# 13thISE_ver2.net
KiCad netlist of a schematic drawn in EAGLE
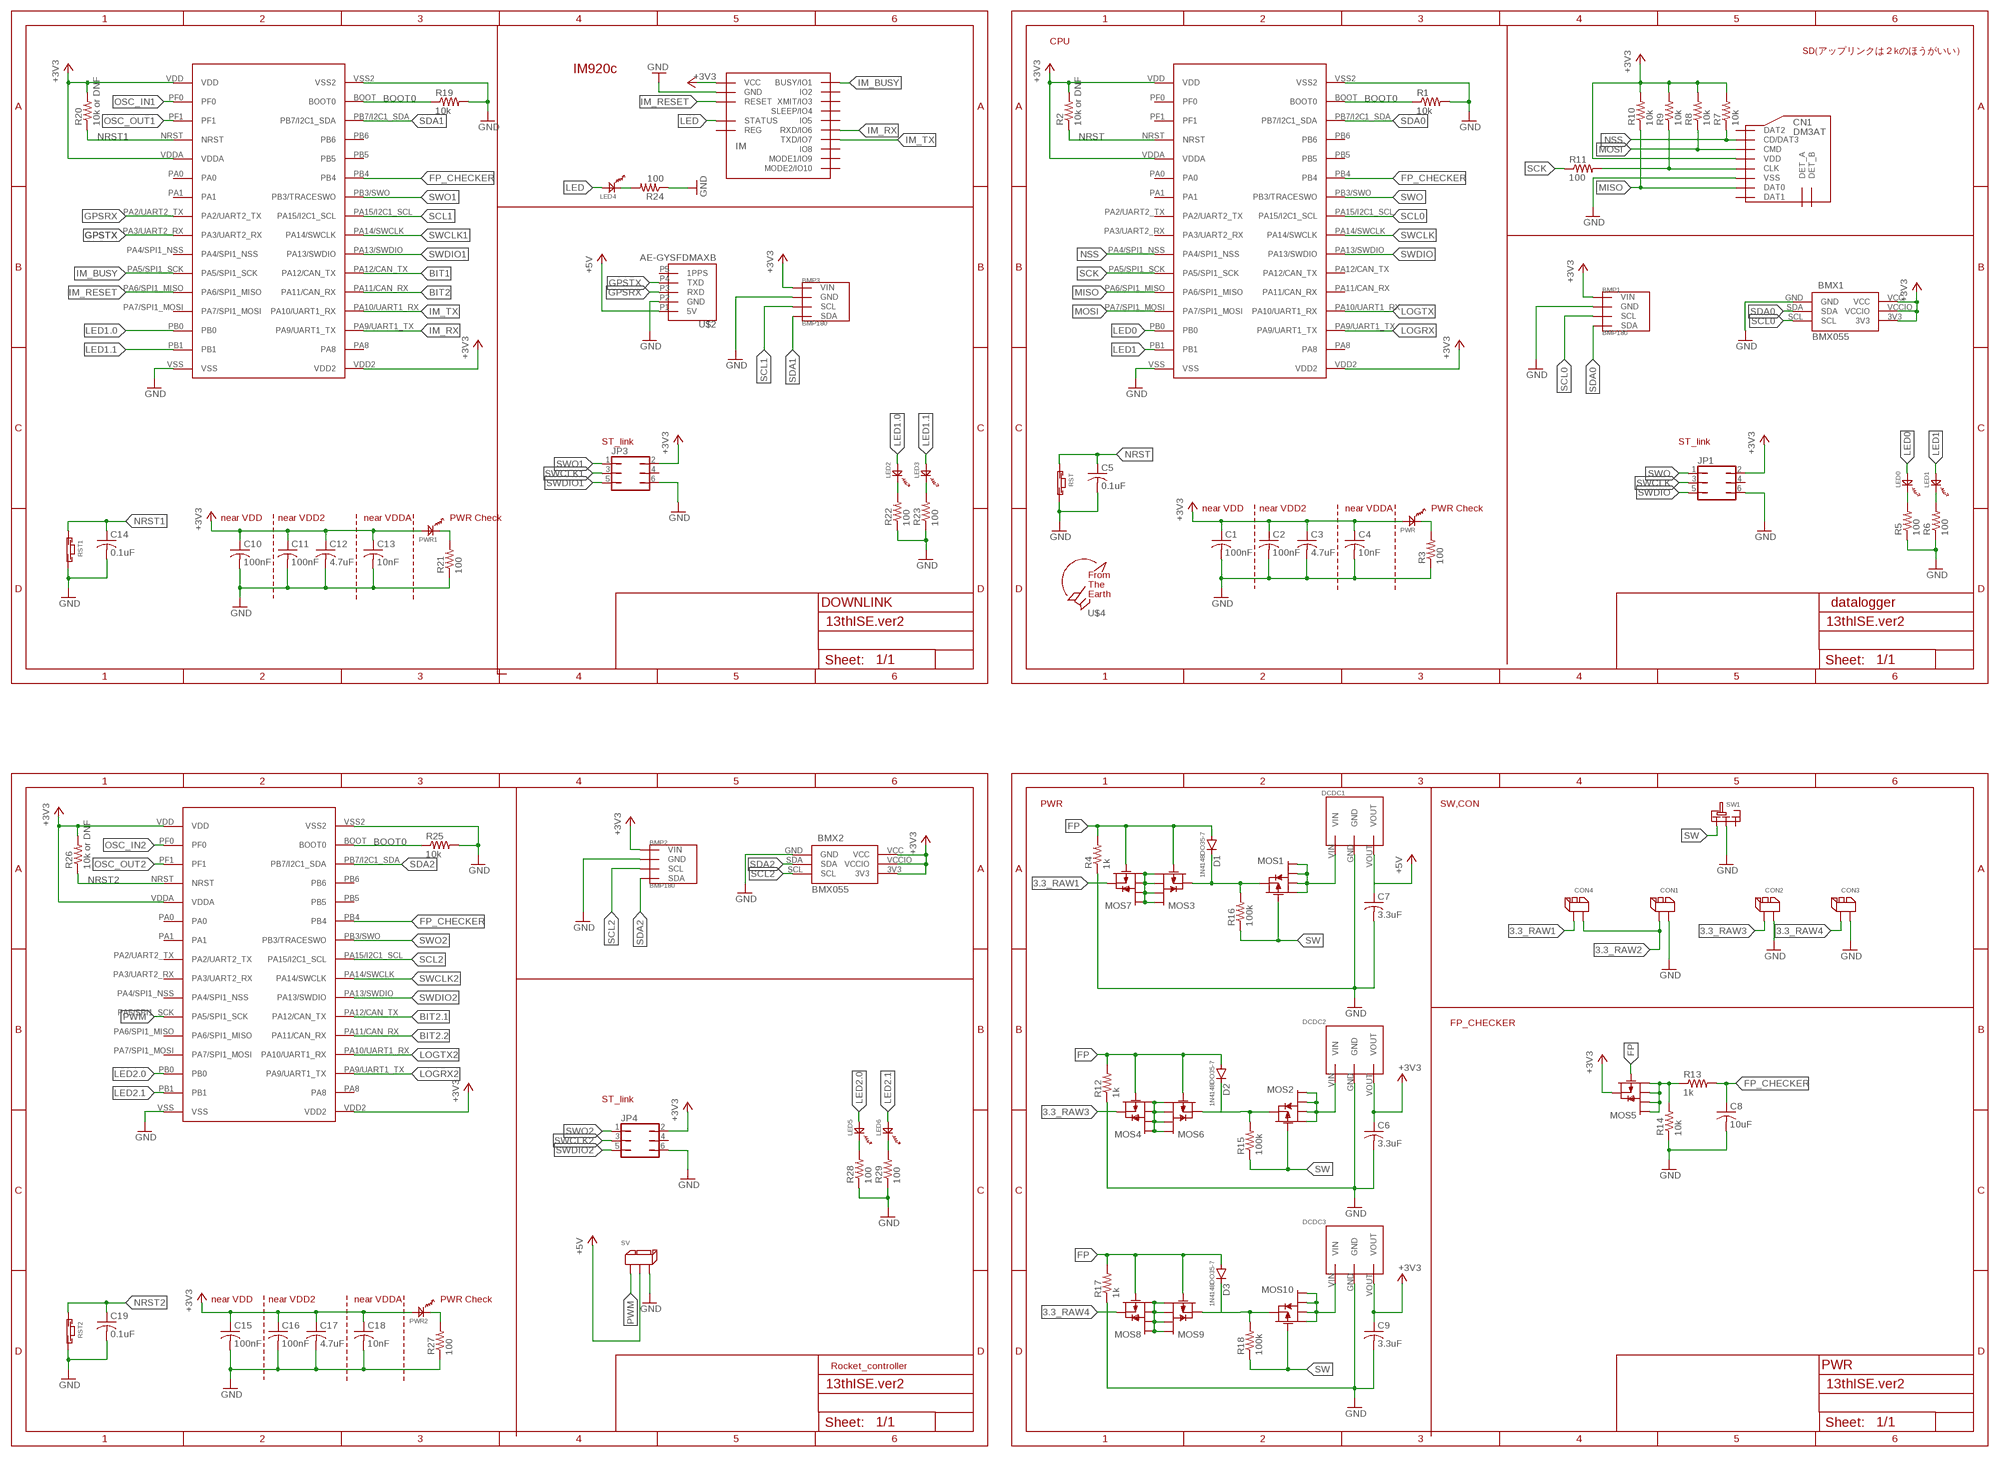
[diagram p0: schematic, sheet 1]

(export (version "E")
  (design (tool "Eeschema 10.0.6"))
  (components
    (comp (ref "BMP1")
      (value "BMP180")
      (footprint "eagle-import:GY-68")
      (libsource (lib "eagle-import") (part "BMP180"))
    )
    (comp (ref "BMP2")
      (value "BMP180")
      (footprint "eagle-import:GY-68")
      (libsource (lib "eagle-import") (part "BMP180"))
    )
    (comp (ref "BMP3")
      (value "BMP180")
      (footprint "eagle-import:GY-68")
      (libsource (lib "eagle-import") (part "BMP180"))
    )
    (comp (ref "BMX1")
      (value "BMX055")
      (footprint "eagle-import:BMX055")
      (libsource (lib "eagle-import") (part "BMX055"))
    )
    (comp (ref "BMX2")
      (value "BMX055")
      (footprint "eagle-import:BMX055")
      (libsource (lib "eagle-import") (part "BMX055"))
    )
    (comp (ref "C1")
      (value "100nF")
      (footprint "eagle-import:C1608")
      (libsource (lib "eagle-import") (part "C-USC1608"))
    )
    (comp (ref "C2")
      (value "100nF")
      (footprint "eagle-import:C1608")
      (libsource (lib "eagle-import") (part "C-USC1608"))
    )
    (comp (ref "C3")
      (value "4.7uF")
      (footprint "eagle-import:C1608")
      (libsource (lib "eagle-import") (part "C-USC1608"))
    )
    (comp (ref "C4")
      (value "10nF")
      (footprint "eagle-import:C1608")
      (libsource (lib "eagle-import") (part "C-USC1608"))
    )
    (comp (ref "C5")
      (value "0.1uF")
      (footprint "eagle-import:C1608")
      (libsource (lib "eagle-import") (part "C-USC1608"))
    )
    (comp (ref "C6")
      (value "3.3uF")
      (footprint "eagle-import:C0603")
      (libsource (lib "eagle-import") (part "C-USC0603"))
    )
    (comp (ref "C7")
      (value "3.3uF")
      (footprint "eagle-import:C0603")
      (libsource (lib "eagle-import") (part "C-USC0603"))
    )
    (comp (ref "C8")
      (value "10uF")
      (footprint "eagle-import:C0603")
      (libsource (lib "eagle-import") (part "C-USC0603"))
    )
    (comp (ref "C9")
      (value "3.3uF")
      (footprint "eagle-import:C0603")
      (libsource (lib "eagle-import") (part "C-USC0603"))
    )
    (comp (ref "C10")
      (value "100nF")
      (footprint "eagle-import:C1608")
      (libsource (lib "eagle-import") (part "C-USC1608"))
    )
    (comp (ref "C11")
      (value "100nF")
      (footprint "eagle-import:C1608")
      (libsource (lib "eagle-import") (part "C-USC1608"))
    )
    (comp (ref "C12")
      (value "4.7uF")
      (footprint "eagle-import:C1608")
      (libsource (lib "eagle-import") (part "C-USC1608"))
    )
    (comp (ref "C13")
      (value "10nF")
      (footprint "eagle-import:C1608")
      (libsource (lib "eagle-import") (part "C-USC1608"))
    )
    (comp (ref "C14")
      (value "0.1uF")
      (footprint "eagle-import:C1608")
      (libsource (lib "eagle-import") (part "C-USC1608"))
    )
    (comp (ref "C15")
      (value "100nF")
      (footprint "eagle-import:C1608")
      (libsource (lib "eagle-import") (part "C-USC1608"))
    )
    (comp (ref "C16")
      (value "100nF")
      (footprint "eagle-import:C1608")
      (libsource (lib "eagle-import") (part "C-USC1608"))
    )
    (comp (ref "C17")
      (value "4.7uF")
      (footprint "eagle-import:C1608")
      (libsource (lib "eagle-import") (part "C-USC1608"))
    )
    (comp (ref "C18")
      (value "10nF")
      (footprint "eagle-import:C1608")
      (libsource (lib "eagle-import") (part "C-USC1608"))
    )
    (comp (ref "C19")
      (value "0.1uF")
      (footprint "eagle-import:C1608")
      (libsource (lib "eagle-import") (part "C-USC1608"))
    )
    (comp (ref "CN1")
      (value "DM3AT")
      (footprint "eagle-import:DM3AT")
      (libsource (lib "eagle-import") (part "DM3AT"))
    )
    (comp (ref "CON1")
      (value "2PIN")
      (footprint "eagle-import:2PIN")
      (libsource (lib "eagle-import") (part "2PIN"))
    )
    (comp (ref "CON2")
      (value "2PIN")
      (footprint "eagle-import:2PIN")
      (libsource (lib "eagle-import") (part "2PIN"))
    )
    (comp (ref "CON3")
      (value "2PIN")
      (footprint "eagle-import:2PIN")
      (libsource (lib "eagle-import") (part "2PIN"))
    )
    (comp (ref "CON4")
      (value "2PIN")
      (footprint "eagle-import:2PIN")
      (libsource (lib "eagle-import") (part "2PIN"))
    )
    (comp (ref "D1")
      (value "1N4148DO35-7")
      (footprint "eagle-import:DO35-7")
      (libsource (lib "eagle-import") (part "1N4148DO35-7"))
    )
    (comp (ref "D2")
      (value "1N4148DO35-7")
      (footprint "eagle-import:DO35-7")
      (libsource (lib "eagle-import") (part "1N4148DO35-7"))
    )
    (comp (ref "D3")
      (value "1N4148DO35-7")
      (footprint "eagle-import:DO35-7")
      (libsource (lib "eagle-import") (part "1N4148DO35-7"))
    )
    (comp (ref "DCDC1")
      (value "5V1A_M78AR05-1")
      (footprint "eagle-import:5V1A_M78AR05-1")
      (libsource (lib "eagle-import") (part "5V1A_M78AR05-1"))
    )
    (comp (ref "DCDC2")
      (value "3.3V1A_M78AR033-1")
      (footprint "eagle-import:3.3V1A_M78AR033-1")
      (libsource (lib "eagle-import") (part "3.3V1A_M78AR033-1"))
    )
    (comp (ref "DCDC3")
      (value "3.3V1A_M78AR033-1")
      (footprint "eagle-import:3.3V1A_M78AR033-1")
      (libsource (lib "eagle-import") (part "3.3V1A_M78AR033-1"))
    )
    (comp (ref "IM")
      (value "IM920C")
      (footprint "eagle-import:IM920C")
      (libsource (lib "eagle-import") (part "IM920C"))
    )
    (comp (ref "JP1")
      (value "JP3Q")
      (footprint "eagle-import:JP3Q")
      (libsource (lib "eagle-import") (part "JP3Q"))
    )
    (comp (ref "JP3")
      (value "JP3Q")
      (footprint "eagle-import:JP3Q")
      (libsource (lib "eagle-import") (part "JP3Q"))
    )
    (comp (ref "JP4")
      (value "JP3Q")
      (footprint "eagle-import:JP3Q")
      (libsource (lib "eagle-import") (part "JP3Q"))
    )
    (comp (ref "LED0")
      (value "OSXX1608C1A")
      (footprint "eagle-import:OSXX1608C1A")
      (libsource (lib "eagle-import") (part "OSXX1608C1A"))
    )
    (comp (ref "LED1")
      (value "OSXX1608C1A")
      (footprint "eagle-import:OSXX1608C1A")
      (libsource (lib "eagle-import") (part "OSXX1608C1A"))
    )
    (comp (ref "LED2")
      (value "OSXX1608C1A")
      (footprint "eagle-import:OSXX1608C1A")
      (libsource (lib "eagle-import") (part "OSXX1608C1A"))
    )
    (comp (ref "LED3")
      (value "OSXX1608C1A")
      (footprint "eagle-import:OSXX1608C1A")
      (libsource (lib "eagle-import") (part "OSXX1608C1A"))
    )
    (comp (ref "LED4")
      (value "OSXX1608C1A")
      (footprint "eagle-import:OSXX1608C1A")
      (libsource (lib "eagle-import") (part "OSXX1608C1A"))
    )
    (comp (ref "LED5")
      (value "OSXX1608C1A")
      (footprint "eagle-import:OSXX1608C1A")
      (libsource (lib "eagle-import") (part "OSXX1608C1A"))
    )
    (comp (ref "LED6")
      (value "OSXX1608C1A")
      (footprint "eagle-import:OSXX1608C1A")
      (libsource (lib "eagle-import") (part "OSXX1608C1A"))
    )
    (comp (ref "MOS1")
      (value "PCH_SSM6J808R")
      (footprint "eagle-import:SSM6J808R")
      (libsource (lib "eagle-import") (part "PCH_SSM6J808R"))
    )
    (comp (ref "MOS2")
      (value "PCH_SSM6J808R")
      (footprint "eagle-import:SSM6J808R")
      (libsource (lib "eagle-import") (part "PCH_SSM6J808R"))
    )
    (comp (ref "MOS3")
      (value "PCH_SSM6J808R")
      (footprint "eagle-import:SSM6J808R")
      (libsource (lib "eagle-import") (part "PCH_SSM6J808R"))
    )
    (comp (ref "MOS4")
      (value "PCH_SSM6J808R")
      (footprint "eagle-import:SSM6J808R")
      (libsource (lib "eagle-import") (part "PCH_SSM6J808R"))
    )
    (comp (ref "MOS5")
      (value "PCH_SSM6J808R")
      (footprint "eagle-import:SSM6J808R")
      (libsource (lib "eagle-import") (part "PCH_SSM6J808R"))
    )
    (comp (ref "MOS6")
      (value "PCH_SSM6J808R")
      (footprint "eagle-import:SSM6J808R")
      (libsource (lib "eagle-import") (part "PCH_SSM6J808R"))
    )
    (comp (ref "MOS7")
      (value "PCH_SSM6J808R")
      (footprint "eagle-import:SSM6J808R")
      (libsource (lib "eagle-import") (part "PCH_SSM6J808R"))
    )
    (comp (ref "MOS8")
      (value "PCH_SSM6J808R")
      (footprint "eagle-import:SSM6J808R")
      (libsource (lib "eagle-import") (part "PCH_SSM6J808R"))
    )
    (comp (ref "MOS9")
      (value "PCH_SSM6J808R")
      (footprint "eagle-import:SSM6J808R")
      (libsource (lib "eagle-import") (part "PCH_SSM6J808R"))
    )
    (comp (ref "MOS10")
      (value "PCH_SSM6J808R")
      (footprint "eagle-import:SSM6J808R")
      (libsource (lib "eagle-import") (part "PCH_SSM6J808R"))
    )
    (comp (ref "PWR")
      (value "OSXX1608C1A")
      (footprint "eagle-import:OSXX1608C1A")
      (libsource (lib "eagle-import") (part "OSXX1608C1A"))
    )
    (comp (ref "PWR1")
      (value "OSXX1608C1A")
      (footprint "eagle-import:OSXX1608C1A")
      (libsource (lib "eagle-import") (part "OSXX1608C1A"))
    )
    (comp (ref "PWR2")
      (value "OSXX1608C1A")
      (footprint "eagle-import:OSXX1608C1A")
      (libsource (lib "eagle-import") (part "OSXX1608C1A"))
    )
    (comp (ref "R1")
      (value "10k")
      (footprint "eagle-import:R0603")
      (libsource (lib "eagle-import") (part "R-US_R0603"))
    )
    (comp (ref "R2")
      (value "10k or DNF")
      (footprint "eagle-import:R0603")
      (libsource (lib "eagle-import") (part "R-US_R0603"))
    )
    (comp (ref "R3")
      (value "100")
      (footprint "eagle-import:R0603")
      (libsource (lib "eagle-import") (part "R-US_R0603"))
    )
    (comp (ref "R4")
      (value "1k")
      (footprint "eagle-import:R0603")
      (libsource (lib "eagle-import") (part "R-US_R0603"))
    )
    (comp (ref "R5")
      (value "100")
      (footprint "eagle-import:R0603")
      (libsource (lib "eagle-import") (part "R-US_R0603"))
    )
    (comp (ref "R6")
      (value "100")
      (footprint "eagle-import:R0603")
      (libsource (lib "eagle-import") (part "R-US_R0603"))
    )
    (comp (ref "R7")
      (value "10k")
      (footprint "eagle-import:R0603")
      (libsource (lib "eagle-import") (part "R-US_R0603"))
    )
    (comp (ref "R8")
      (value "10k")
      (footprint "eagle-import:R0603")
      (libsource (lib "eagle-import") (part "R-US_R0603"))
    )
    (comp (ref "R9")
      (value "10k")
      (footprint "eagle-import:R0603")
      (libsource (lib "eagle-import") (part "R-US_R0603"))
    )
    (comp (ref "R10")
      (value "10k")
      (footprint "eagle-import:R0603")
      (libsource (lib "eagle-import") (part "R-US_R0603"))
    )
    (comp (ref "R11")
      (value "100")
      (footprint "eagle-import:R0603")
      (libsource (lib "eagle-import") (part "R-US_R0603"))
    )
    (comp (ref "R12")
      (value "1k")
      (footprint "eagle-import:R0603")
      (libsource (lib "eagle-import") (part "R-US_R0603"))
    )
    (comp (ref "R13")
      (value "1k")
      (footprint "eagle-import:R0603")
      (libsource (lib "eagle-import") (part "R-US_R0603"))
    )
    (comp (ref "R14")
      (value "10k")
      (footprint "eagle-import:R0603")
      (libsource (lib "eagle-import") (part "R-US_R0603"))
    )
    (comp (ref "R15")
      (value "100k")
      (footprint "eagle-import:R0603")
      (libsource (lib "eagle-import") (part "R-US_R0603"))
    )
    (comp (ref "R16")
      (value "100k")
      (footprint "eagle-import:R0603")
      (libsource (lib "eagle-import") (part "R-US_R0603"))
    )
    (comp (ref "R17")
      (value "1k")
      (footprint "eagle-import:R0603")
      (libsource (lib "eagle-import") (part "R-US_R0603"))
    )
    (comp (ref "R18")
      (value "100k")
      (footprint "eagle-import:R0603")
      (libsource (lib "eagle-import") (part "R-US_R0603"))
    )
    (comp (ref "R19")
      (value "10k")
      (footprint "eagle-import:R0603")
      (libsource (lib "eagle-import") (part "R-US_R0603"))
    )
    (comp (ref "R20")
      (value "10k or DNF")
      (footprint "eagle-import:R0603")
      (libsource (lib "eagle-import") (part "R-US_R0603"))
    )
    (comp (ref "R21")
      (value "100")
      (footprint "eagle-import:R0603")
      (libsource (lib "eagle-import") (part "R-US_R0603"))
    )
    (comp (ref "R22")
      (value "100")
      (footprint "eagle-import:R0603")
      (libsource (lib "eagle-import") (part "R-US_R0603"))
    )
    (comp (ref "R23")
      (value "100")
      (footprint "eagle-import:R0603")
      (libsource (lib "eagle-import") (part "R-US_R0603"))
    )
    (comp (ref "R24")
      (value "100")
      (footprint "eagle-import:R0603")
      (libsource (lib "eagle-import") (part "R-US_R0603"))
    )
    (comp (ref "R25")
      (value "10k")
      (footprint "eagle-import:R0603")
      (libsource (lib "eagle-import") (part "R-US_R0603"))
    )
    (comp (ref "R26")
      (value "10k or DNF")
      (footprint "eagle-import:R0603")
      (libsource (lib "eagle-import") (part "R-US_R0603"))
    )
    (comp (ref "R27")
      (value "100")
      (footprint "eagle-import:R0603")
      (libsource (lib "eagle-import") (part "R-US_R0603"))
    )
    (comp (ref "R28")
      (value "100")
      (footprint "eagle-import:R0603")
      (libsource (lib "eagle-import") (part "R-US_R0603"))
    )
    (comp (ref "R29")
      (value "100")
      (footprint "eagle-import:R0603")
      (libsource (lib "eagle-import") (part "R-US_R0603"))
    )
    (comp (ref "RST")
      (value "TVAF06-A020B-R")
      (footprint "eagle-import:TVAF06-A020B-R")
      (libsource (lib "eagle-import") (part "TVAF06-A020B-R"))
    )
    (comp (ref "RST1")
      (value "TVAF06-A020B-R")
      (footprint "eagle-import:TVAF06-A020B-R")
      (libsource (lib "eagle-import") (part "TVAF06-A020B-R"))
    )
    (comp (ref "RST2")
      (value "TVAF06-A020B-R")
      (footprint "eagle-import:TVAF06-A020B-R")
      (libsource (lib "eagle-import") (part "TVAF06-A020B-R"))
    )
    (comp (ref "STM0")
      (value "STM32F303K8")
      (footprint "eagle-import:STM32F303K8")
      (libsource (lib "eagle-import") (part "STM32F303K8"))
    )
    (comp (ref "STM1")
      (value "STM32F303K8")
      (footprint "eagle-import:STM32F303K8")
      (libsource (lib "eagle-import") (part "STM32F303K8"))
    )
    (comp (ref "SV")
      (value "3PIN")
      (footprint "eagle-import:3PIN")
      (libsource (lib "eagle-import") (part "3PIN"))
    )
    (comp (ref "SW1")
      (value "SRIDE_SWITCH")
      (footprint "eagle-import:SRIDE_SWITCH")
      (libsource (lib "eagle-import") (part "SRIDE_SWITCH"))
    )
    (comp (ref "U$1")
      (value "STM32F303K8")
      (footprint "eagle-import:STM32F303K8")
      (libsource (lib "eagle-import") (part "STM32F303K8"))
    )
    (comp (ref "U$2")
      (value "AE-GYSFDMAXB")
      (footprint "eagle-import:AE-GYSFDMAXB")
      (libsource (lib "eagle-import") (part "AE-GYSFDMAXB"))
    )
    (comp (ref "U$4")
      (value "F.T.E.LOGO")
      (footprint "eagle-import:LOGO")
      (libsource (lib "eagle-import") (part "F.T.E.LOGO"))
    )
  )
  (nets
    (net (code "1") (name "+3V3") (class "Default")
      (node (ref "BMP1") (pin "P1") (pinfunction "VIN_P1") (pintype "bidirectional"))
      (node (ref "BMP2") (pin "P1") (pinfunction "VIN_P1") (pintype "bidirectional"))
      (node (ref "BMP3") (pin "P1") (pinfunction "VIN_P1") (pintype "bidirectional"))
      (node (ref "BMX1") (pin "3V3") (pinfunction "3V3_3V3") (pintype "power_in"))
      (node (ref "BMX1") (pin "VCC") (pinfunction "VCC_VCC") (pintype "power_in"))
      (node (ref "BMX1") (pin "VCCIO") (pinfunction "VCCIO_VCCIO") (pintype "power_in"))
      (node (ref "BMX2") (pin "3V3") (pinfunction "3V3_3V3") (pintype "power_in"))
      (node (ref "BMX2") (pin "VCC") (pinfunction "VCC_VCC") (pintype "power_in"))
      (node (ref "BMX2") (pin "VCCIO") (pinfunction "VCCIO_VCCIO") (pintype "power_in"))
      (node (ref "C1") (pin "1") (pinfunction "1_1") (pintype "passive"))
      (node (ref "C10") (pin "1") (pinfunction "1_1") (pintype "passive"))
      (node (ref "C11") (pin "1") (pinfunction "1_1") (pintype "passive"))
      (node (ref "C12") (pin "1") (pinfunction "1_1") (pintype "passive"))
      (node (ref "C13") (pin "1") (pinfunction "1_1") (pintype "passive"))
      (node (ref "C15") (pin "1") (pinfunction "1_1") (pintype "passive"))
      (node (ref "C16") (pin "1") (pinfunction "1_1") (pintype "passive"))
      (node (ref "C17") (pin "1") (pinfunction "1_1") (pintype "passive"))
      (node (ref "C18") (pin "1") (pinfunction "1_1") (pintype "passive"))
      (node (ref "C2") (pin "1") (pinfunction "1_1") (pintype "passive"))
      (node (ref "C3") (pin "1") (pinfunction "1_1") (pintype "passive"))
      (node (ref "C4") (pin "1") (pinfunction "1_1") (pintype "passive"))
      (node (ref "C6") (pin "1") (pinfunction "1_1") (pintype "passive"))
      (node (ref "C9") (pin "1") (pinfunction "1_1") (pintype "passive"))
      (node (ref "CN1") (pin "VDD") (pinfunction "VDD_VDD") (pintype "bidirectional"))
      (node (ref "DCDC2") (pin "VOUT") (pinfunction "VOUT_VOUT") (pintype "bidirectional"))
      (node (ref "DCDC3") (pin "VOUT") (pinfunction "VOUT_VOUT") (pintype "bidirectional"))
      (node (ref "IM") (pin "$P17") (pinfunction "VCC_$P17") (pintype "bidirectional"))
      (node (ref "JP1") (pin "2") (pinfunction "2_2") (pintype "passive"))
      (node (ref "JP3") (pin "2") (pinfunction "2_2") (pintype "passive"))
      (node (ref "JP4") (pin "2") (pinfunction "2_2") (pintype "passive"))
      (node (ref "MOS5") (pin "4") (pinfunction "4_4") (pintype "bidirectional"))
      (node (ref "PWR") (pin "AN") (pinfunction "AN_AN") (pintype "bidirectional"))
      (node (ref "PWR1") (pin "AN") (pinfunction "AN_AN") (pintype "bidirectional"))
      (node (ref "PWR2") (pin "AN") (pinfunction "AN_AN") (pintype "bidirectional"))
      (node (ref "R10") (pin "2") (pinfunction "2_2") (pintype "passive"))
      (node (ref "R2") (pin "2") (pinfunction "2_2") (pintype "passive"))
      (node (ref "R20") (pin "2") (pinfunction "2_2") (pintype "passive"))
      (node (ref "R26") (pin "2") (pinfunction "2_2") (pintype "passive"))
      (node (ref "R7") (pin "2") (pinfunction "2_2") (pintype "passive"))
      (node (ref "R8") (pin "2") (pinfunction "2_2") (pintype "passive"))
      (node (ref "R9") (pin "2") (pinfunction "2_2") (pintype "passive"))
      (node (ref "STM0") (pin "VDD") (pinfunction "VDD_VDD") (pintype "power_in"))
      (node (ref "STM0") (pin "VDD2") (pinfunction "VDD2_VDD2") (pintype "power_in"))
      (node (ref "STM0") (pin "VDDA") (pinfunction "VDDA_VDDA") (pintype "power_in"))
      (node (ref "STM1") (pin "VDD") (pinfunction "VDD_VDD") (pintype "power_in"))
      (node (ref "STM1") (pin "VDD2") (pinfunction "VDD2_VDD2") (pintype "power_in"))
      (node (ref "STM1") (pin "VDDA") (pinfunction "VDDA_VDDA") (pintype "power_in"))
      (node (ref "U$1") (pin "VDD") (pinfunction "VDD_VDD") (pintype "power_in"))
      (node (ref "U$1") (pin "VDD2") (pinfunction "VDD2_VDD2") (pintype "power_in"))
      (node (ref "U$1") (pin "VDDA") (pinfunction "VDDA_VDDA") (pintype "power_in"))
    )
    (net (code "2") (name "+5V") (class "Default")
      (node (ref "C7") (pin "1") (pinfunction "1_1") (pintype "passive"))
      (node (ref "DCDC1") (pin "VOUT") (pinfunction "VOUT_VOUT") (pintype "bidirectional"))
      (node (ref "SV") (pin "P$2") (pinfunction "P$2_P$2") (pintype "bidirectional"))
      (node (ref "U$2") (pin "P1") (pinfunction "5V_P1") (pintype "bidirectional"))
    )
    (net (code "3") (name "/BOOT0") (class "Default")
      (node (ref "R1") (pin "1") (pinfunction "1_1") (pintype "passive"))
      (node (ref "R19") (pin "1") (pinfunction "1_1") (pintype "passive"))
      (node (ref "R25") (pin "1") (pinfunction "1_1") (pintype "passive"))
      (node (ref "STM0") (pin "BOOT") (pinfunction "BOOT0_BOOT") (pintype "bidirectional"))
      (node (ref "STM1") (pin "BOOT") (pinfunction "BOOT0_BOOT") (pintype "bidirectional"))
      (node (ref "U$1") (pin "BOOT") (pinfunction "BOOT0_BOOT") (pintype "bidirectional"))
    )
    (net (code "4") (name "3.3_RAW1") (class "Default")
      (node (ref "CON4") (pin "P$2") (pinfunction "P$2_P$2") (pintype "bidirectional"))
      (node (ref "MOS7") (pin "4") (pinfunction "4_4") (pintype "bidirectional"))
    )
    (net (code "5") (name "3.3_RAW2") (class "Default")
      (node (ref "CON1") (pin "P$2") (pinfunction "P$2_P$2") (pintype "bidirectional"))
      (node (ref "CON4") (pin "P$1") (pinfunction "P$1_P$1") (pintype "bidirectional"))
    )
    (net (code "6") (name "3.3_RAW3") (class "Default")
      (node (ref "CON2") (pin "P$2") (pinfunction "P$2_P$2") (pintype "bidirectional"))
      (node (ref "MOS4") (pin "4") (pinfunction "4_4") (pintype "bidirectional"))
    )
    (net (code "7") (name "3.3_RAW4") (class "Default")
      (node (ref "CON3") (pin "P$2") (pinfunction "P$2_P$2") (pintype "bidirectional"))
      (node (ref "MOS8") (pin "4") (pinfunction "4_4") (pintype "bidirectional"))
    )
    (net (code "8") (name "BIT1") (class "Default")
      (node (ref "STM1") (pin "PA12/CAN_TX") (pinfunction "PA12/CAN_TX_PA12/CAN_TX") (pintype "bidirectional"))
    )
    (net (code "9") (name "BIT2") (class "Default")
      (node (ref "STM1") (pin "PA11/CAN_RX") (pinfunction "PA11/CAN_RX_PA11/CAN_RX") (pintype "bidirectional"))
    )
    (net (code "10") (name "BIT2.1") (class "Default")
      (node (ref "U$1") (pin "PA12/CAN_TX") (pinfunction "PA12/CAN_TX_PA12/CAN_TX") (pintype "bidirectional"))
    )
    (net (code "11") (name "BIT2.2") (class "Default")
      (node (ref "U$1") (pin "PA11/CAN_RX") (pinfunction "PA11/CAN_RX_PA11/CAN_RX") (pintype "bidirectional"))
    )
    (net (code "12") (name "FP") (class "Default")
      (node (ref "D1") (pin "A") (pinfunction "A_A") (pintype "passive"))
      (node (ref "D2") (pin "A") (pinfunction "A_A") (pintype "passive"))
      (node (ref "D3") (pin "A") (pinfunction "A_A") (pintype "passive"))
      (node (ref "MOS3") (pin "3") (pinfunction "3_3") (pintype "bidirectional"))
      (node (ref "MOS4") (pin "3") (pinfunction "3_3") (pintype "bidirectional"))
      (node (ref "MOS5") (pin "3") (pinfunction "3_3") (pintype "bidirectional"))
      (node (ref "MOS6") (pin "3") (pinfunction "3_3") (pintype "bidirectional"))
      (node (ref "MOS7") (pin "3") (pinfunction "3_3") (pintype "bidirectional"))
      (node (ref "MOS8") (pin "3") (pinfunction "3_3") (pintype "bidirectional"))
      (node (ref "MOS9") (pin "3") (pinfunction "3_3") (pintype "bidirectional"))
      (node (ref "R12") (pin "2") (pinfunction "2_2") (pintype "passive"))
      (node (ref "R17") (pin "2") (pinfunction "2_2") (pintype "passive"))
      (node (ref "R4") (pin "2") (pinfunction "2_2") (pintype "passive"))
    )
    (net (code "13") (name "FP_CHECKER") (class "Default")
      (node (ref "C8") (pin "1") (pinfunction "1_1") (pintype "passive"))
      (node (ref "R13") (pin "2") (pinfunction "2_2") (pintype "passive"))
      (node (ref "STM0") (pin "PB4") (pinfunction "PB4_PB4") (pintype "bidirectional"))
      (node (ref "STM1") (pin "PB4") (pinfunction "PB4_PB4") (pintype "bidirectional"))
      (node (ref "U$1") (pin "PB4") (pinfunction "PB4_PB4") (pintype "bidirectional"))
    )
    (net (code "14") (name "GND") (class "Default")
      (node (ref "BMP1") (pin "P2") (pinfunction "GND_P2") (pintype "bidirectional"))
      (node (ref "BMP2") (pin "P2") (pinfunction "GND_P2") (pintype "bidirectional"))
      (node (ref "BMP3") (pin "P2") (pinfunction "GND_P2") (pintype "bidirectional"))
      (node (ref "BMX1") (pin "GND") (pinfunction "GND_GND") (pintype "power_in"))
      (node (ref "BMX2") (pin "GND") (pinfunction "GND_GND") (pintype "power_in"))
      (node (ref "C1") (pin "2") (pinfunction "2_2") (pintype "passive"))
      (node (ref "C10") (pin "2") (pinfunction "2_2") (pintype "passive"))
      (node (ref "C11") (pin "2") (pinfunction "2_2") (pintype "passive"))
      (node (ref "C12") (pin "2") (pinfunction "2_2") (pintype "passive"))
      (node (ref "C13") (pin "2") (pinfunction "2_2") (pintype "passive"))
      (node (ref "C14") (pin "2") (pinfunction "2_2") (pintype "passive"))
      (node (ref "C15") (pin "2") (pinfunction "2_2") (pintype "passive"))
      (node (ref "C16") (pin "2") (pinfunction "2_2") (pintype "passive"))
      (node (ref "C17") (pin "2") (pinfunction "2_2") (pintype "passive"))
      (node (ref "C18") (pin "2") (pinfunction "2_2") (pintype "passive"))
      (node (ref "C19") (pin "2") (pinfunction "2_2") (pintype "passive"))
      (node (ref "C2") (pin "2") (pinfunction "2_2") (pintype "passive"))
      (node (ref "C3") (pin "2") (pinfunction "2_2") (pintype "passive"))
      (node (ref "C4") (pin "2") (pinfunction "2_2") (pintype "passive"))
      (node (ref "C5") (pin "2") (pinfunction "2_2") (pintype "passive"))
      (node (ref "C6") (pin "2") (pinfunction "2_2") (pintype "passive"))
      (node (ref "C7") (pin "2") (pinfunction "2_2") (pintype "passive"))
      (node (ref "C8") (pin "2") (pinfunction "2_2") (pintype "passive"))
      (node (ref "C9") (pin "2") (pinfunction "2_2") (pintype "passive"))
      (node (ref "CN1") (pin "VSS") (pinfunction "VSS_VSS") (pintype "bidirectional"))
      (node (ref "CON1") (pin "P$1") (pinfunction "P$1_P$1") (pintype "bidirectional"))
      (node (ref "CON2") (pin "P$1") (pinfunction "P$1_P$1") (pintype "bidirectional"))
      (node (ref "CON3") (pin "P$1") (pinfunction "P$1_P$1") (pintype "bidirectional"))
      (node (ref "DCDC1") (pin "GND") (pinfunction "GND_GND") (pintype "bidirectional"))
      (node (ref "DCDC2") (pin "GND") (pinfunction "GND_GND") (pintype "bidirectional"))
      (node (ref "DCDC3") (pin "GND") (pinfunction "GND_GND") (pintype "bidirectional"))
      (node (ref "IM") (pin "$P18") (pinfunction "GND_$P18") (pintype "bidirectional"))
      (node (ref "JP1") (pin "6") (pinfunction "6_6") (pintype "passive"))
      (node (ref "JP3") (pin "6") (pinfunction "6_6") (pintype "passive"))
      (node (ref "JP4") (pin "6") (pinfunction "6_6") (pintype "passive"))
      (node (ref "R1") (pin "2") (pinfunction "2_2") (pintype "passive"))
      (node (ref "R12") (pin "1") (pinfunction "1_1") (pintype "passive"))
      (node (ref "R14") (pin "1") (pinfunction "1_1") (pintype "passive"))
      (node (ref "R17") (pin "1") (pinfunction "1_1") (pintype "passive"))
      (node (ref "R19") (pin "2") (pinfunction "2_2") (pintype "passive"))
      (node (ref "R21") (pin "1") (pinfunction "1_1") (pintype "passive"))
      (node (ref "R22") (pin "1") (pinfunction "1_1") (pintype "passive"))
      (node (ref "R23") (pin "1") (pinfunction "1_1") (pintype "passive"))
      (node (ref "R24") (pin "1") (pinfunction "1_1") (pintype "passive"))
      (node (ref "R25") (pin "2") (pinfunction "2_2") (pintype "passive"))
      (node (ref "R27") (pin "1") (pinfunction "1_1") (pintype "passive"))
      (node (ref "R28") (pin "1") (pinfunction "1_1") (pintype "passive"))
      (node (ref "R29") (pin "1") (pinfunction "1_1") (pintype "passive"))
      (node (ref "R3") (pin "1") (pinfunction "1_1") (pintype "passive"))
      (node (ref "R4") (pin "1") (pinfunction "1_1") (pintype "passive"))
      (node (ref "R5") (pin "1") (pinfunction "1_1") (pintype "passive"))
      (node (ref "R6") (pin "1") (pinfunction "1_1") (pintype "passive"))
      (node (ref "RST") (pin "P$2") (pinfunction "P$2_P$2") (pintype "bidirectional"))
      (node (ref "RST1") (pin "P$2") (pinfunction "P$2_P$2") (pintype "bidirectional"))
      (node (ref "RST2") (pin "P$2") (pinfunction "P$2_P$2") (pintype "bidirectional"))
      (node (ref "STM0") (pin "VSS") (pinfunction "VSS_VSS") (pintype "power_in"))
      (node (ref "STM0") (pin "VSS2") (pinfunction "VSS2_VSS2") (pintype "power_in"))
      (node (ref "STM1") (pin "VSS") (pinfunction "VSS_VSS") (pintype "power_in"))
      (node (ref "STM1") (pin "VSS2") (pinfunction "VSS2_VSS2") (pintype "power_in"))
      (node (ref "SV") (pin "P$3") (pinfunction "P$3_P$3") (pintype "bidirectional"))
      (node (ref "SW1") (pin "LR") (pinfunction "LR_LR") (pintype "bidirectional"))
      (node (ref "U$1") (pin "VSS") (pinfunction "VSS_VSS") (pintype "power_in"))
      (node (ref "U$1") (pin "VSS2") (pinfunction "VSS2_VSS2") (pintype "power_in"))
      (node (ref "U$2") (pin "P2") (pinfunction "GND_P2") (pintype "bidirectional"))
    )
    (net (code "15") (name "GPSRX") (class "Default")
      (node (ref "STM1") (pin "PA2/UART2_TX") (pinfunction "PA2/UART2_TX_PA2/UART2_TX") (pintype "bidirectional"))
      (node (ref "U$2") (pin "P3") (pinfunction "RXD_P3") (pintype "bidirectional"))
    )
    (net (code "16") (name "GPSTX") (class "Default")
      (node (ref "STM1") (pin "PA3/UART2_RX") (pinfunction "PA3/UART2_RX_PA3/UART2_RX") (pintype "bidirectional"))
      (node (ref "U$2") (pin "P4") (pinfunction "TXD_P4") (pintype "bidirectional"))
    )
    (net (code "17") (name "IM_BUSY") (class "Default")
      (node (ref "IM") (pin "$P1") (pinfunction "BUSY/IO1_$P1") (pintype "bidirectional"))
      (node (ref "STM1") (pin "PA5/SPI1_SCK") (pinfunction "PA5/SPI1_SCK_PA5/SPI1_SCK") (pintype "bidirectional"))
    )
    (net (code "18") (name "IM_RESET") (class "Default")
      (node (ref "IM") (pin "$P19") (pinfunction "RESET_$P19") (pintype "bidirectional"))
      (node (ref "STM1") (pin "PA6/SPI1_MISO") (pinfunction "PA6/SPI1_MISO_PA6/SPI1_MISO") (pintype "bidirectional"))
    )
    (net (code "19") (name "IM_RX") (class "Default")
      (node (ref "IM") (pin "$P6") (pinfunction "RXD/IO6_$P6") (pintype "bidirectional"))
      (node (ref "STM1") (pin "PA9/UART1_TX") (pinfunction "PA9/UART1_TX_PA9/UART1_TX") (pintype "bidirectional"))
    )
    (net (code "20") (name "IM_TX") (class "Default")
      (node (ref "IM") (pin "$P7") (pinfunction "TXD/IO7_$P7") (pintype "bidirectional"))
      (node (ref "STM1") (pin "PA10/UART1_RX") (pinfunction "PA10/UART1_RX_PA10/UART1_RX") (pintype "bidirectional"))
    )
    (net (code "21") (name "LED") (class "Default")
      (node (ref "IM") (pin "$P15") (pinfunction "STATUS_$P15") (pintype "bidirectional"))
      (node (ref "LED4") (pin "AN") (pinfunction "AN_AN") (pintype "bidirectional"))
    )
    (net (code "22") (name "LED0") (class "Default")
      (node (ref "LED0") (pin "AN") (pinfunction "AN_AN") (pintype "bidirectional"))
      (node (ref "STM0") (pin "PB0") (pinfunction "PB0_PB0") (pintype "bidirectional"))
    )
    (net (code "23") (name "LED1") (class "Default")
      (node (ref "LED1") (pin "AN") (pinfunction "AN_AN") (pintype "bidirectional"))
      (node (ref "STM0") (pin "PB1") (pinfunction "PB1_PB1") (pintype "bidirectional"))
    )
    (net (code "24") (name "LED1.0") (class "Default")
      (node (ref "LED2") (pin "AN") (pinfunction "AN_AN") (pintype "bidirectional"))
      (node (ref "STM1") (pin "PB0") (pinfunction "PB0_PB0") (pintype "bidirectional"))
    )
    (net (code "25") (name "LED1.1") (class "Default")
      (node (ref "LED3") (pin "AN") (pinfunction "AN_AN") (pintype "bidirectional"))
      (node (ref "STM1") (pin "PB1") (pinfunction "PB1_PB1") (pintype "bidirectional"))
    )
    (net (code "26") (name "LED2.0") (class "Default")
      (node (ref "LED5") (pin "AN") (pinfunction "AN_AN") (pintype "bidirectional"))
      (node (ref "U$1") (pin "PB0") (pinfunction "PB0_PB0") (pintype "bidirectional"))
    )
    (net (code "27") (name "LED2.1") (class "Default")
      (node (ref "LED6") (pin "AN") (pinfunction "AN_AN") (pintype "bidirectional"))
      (node (ref "U$1") (pin "PB1") (pinfunction "PB1_PB1") (pintype "bidirectional"))
    )
    (net (code "28") (name "LOGRX") (class "Default")
      (node (ref "STM0") (pin "PA9/UART1_TX") (pinfunction "PA9/UART1_TX_PA9/UART1_TX") (pintype "bidirectional"))
    )
    (net (code "29") (name "LOGRX2") (class "Default")
      (node (ref "U$1") (pin "PA9/UART1_TX") (pinfunction "PA9/UART1_TX_PA9/UART1_TX") (pintype "bidirectional"))
    )
    (net (code "30") (name "LOGTX") (class "Default")
      (node (ref "STM0") (pin "PA10/UART1_RX") (pinfunction "PA10/UART1_RX_PA10/UART1_RX") (pintype "bidirectional"))
    )
    (net (code "31") (name "LOGTX2") (class "Default")
      (node (ref "U$1") (pin "PA10/UART1_RX") (pinfunction "PA10/UART1_RX_PA10/UART1_RX") (pintype "bidirectional"))
    )
    (net (code "32") (name "MISO") (class "Default")
      (node (ref "CN1") (pin "DAT0") (pinfunction "DAT0_DAT0") (pintype "bidirectional"))
      (node (ref "R10") (pin "1") (pinfunction "1_1") (pintype "passive"))
      (node (ref "STM0") (pin "PA6/SPI1_MISO") (pinfunction "PA6/SPI1_MISO_PA6/SPI1_MISO") (pintype "bidirectional"))
    )
    (net (code "33") (name "MOSI") (class "Default")
      (node (ref "CN1") (pin "CMD") (pinfunction "CMD_CMD") (pintype "bidirectional"))
      (node (ref "R8") (pin "1") (pinfunction "1_1") (pintype "passive"))
      (node (ref "STM0") (pin "PA7/SPI1_MOSI") (pinfunction "PA7/SPI1_MOSI_PA7/SPI1_MOSI") (pintype "bidirectional"))
    )
    (net (code "34") (name "NRST") (class "Default")
      (node (ref "C5") (pin "1") (pinfunction "1_1") (pintype "passive"))
      (node (ref "R2") (pin "1") (pinfunction "1_1") (pintype "passive"))
      (node (ref "RST") (pin "P$1") (pinfunction "P$1_P$1") (pintype "bidirectional"))
      (node (ref "STM0") (pin "NRST") (pinfunction "NRST_NRST") (pintype "bidirectional"))
    )
    (net (code "35") (name "NRST1") (class "Default")
      (node (ref "C14") (pin "1") (pinfunction "1_1") (pintype "passive"))
      (node (ref "R20") (pin "1") (pinfunction "1_1") (pintype "passive"))
      (node (ref "RST1") (pin "P$1") (pinfunction "P$1_P$1") (pintype "bidirectional"))
      (node (ref "STM1") (pin "NRST") (pinfunction "NRST_NRST") (pintype "bidirectional"))
    )
    (net (code "36") (name "NRST2") (class "Default")
      (node (ref "C19") (pin "1") (pinfunction "1_1") (pintype "passive"))
      (node (ref "R26") (pin "1") (pinfunction "1_1") (pintype "passive"))
      (node (ref "RST2") (pin "P$1") (pinfunction "P$1_P$1") (pintype "bidirectional"))
      (node (ref "U$1") (pin "NRST") (pinfunction "NRST_NRST") (pintype "bidirectional"))
    )
    (net (code "37") (name "NSS") (class "Default")
      (node (ref "CN1") (pin "CD/DAT3") (pinfunction "CD/DAT3_CD/DAT3") (pintype "bidirectional"))
      (node (ref "R7") (pin "1") (pinfunction "1_1") (pintype "passive"))
      (node (ref "STM0") (pin "PA4/SPI1_NSS") (pinfunction "PA4/SPI1_NSS_PA4/SPI1_NSS") (pintype "bidirectional"))
    )
    (net (code "38") (name "Net-(CN1-PadCLK)") (class "Default")
      (node (ref "CN1") (pin "CLK") (pinfunction "CLK_CLK") (pintype "bidirectional"))
      (node (ref "R11") (pin "2") (pinfunction "2_2") (pintype "passive"))
      (node (ref "R9") (pin "1") (pinfunction "1_1") (pintype "passive"))
    )
    (net (code "39") (name "Net-(D1-PadC)") (class "Default")
      (node (ref "D1") (pin "C") (pinfunction "C_C") (pintype "passive"))
      (node (ref "MOS1") (pin "4") (pinfunction "4_4") (pintype "bidirectional"))
      (node (ref "MOS3") (pin "4") (pinfunction "4_4") (pintype "bidirectional"))
      (node (ref "R16") (pin "2") (pinfunction "2_2") (pintype "passive"))
    )
    (net (code "40") (name "Net-(D2-PadC)") (class "Default")
      (node (ref "D2") (pin "C") (pinfunction "C_C") (pintype "passive"))
      (node (ref "MOS2") (pin "4") (pinfunction "4_4") (pintype "bidirectional"))
      (node (ref "MOS6") (pin "4") (pinfunction "4_4") (pintype "bidirectional"))
      (node (ref "R15") (pin "2") (pinfunction "2_2") (pintype "passive"))
    )
    (net (code "41") (name "Net-(D3-PadC)") (class "Default")
      (node (ref "D3") (pin "C") (pinfunction "C_C") (pintype "passive"))
      (node (ref "MOS10") (pin "4") (pinfunction "4_4") (pintype "bidirectional"))
      (node (ref "MOS9") (pin "4") (pinfunction "4_4") (pintype "bidirectional"))
      (node (ref "R18") (pin "2") (pinfunction "2_2") (pintype "passive"))
    )
    (net (code "42") (name "Net-(DCDC1-PadVIN)") (class "Default")
      (node (ref "DCDC1") (pin "VIN") (pinfunction "VIN_VIN") (pintype "bidirectional"))
      (node (ref "MOS1") (pin "1") (pinfunction "1_1") (pintype "bidirectional"))
      (node (ref "MOS1") (pin "2") (pinfunction "2_2") (pintype "bidirectional"))
      (node (ref "MOS1") (pin "5") (pinfunction "5_5") (pintype "bidirectional"))
      (node (ref "MOS1") (pin "6") (pinfunction "6_6") (pintype "bidirectional"))
    )
    (net (code "43") (name "Net-(DCDC2-PadVIN)") (class "Default")
      (node (ref "DCDC2") (pin "VIN") (pinfunction "VIN_VIN") (pintype "bidirectional"))
      (node (ref "MOS2") (pin "1") (pinfunction "1_1") (pintype "bidirectional"))
      (node (ref "MOS2") (pin "2") (pinfunction "2_2") (pintype "bidirectional"))
      (node (ref "MOS2") (pin "5") (pinfunction "5_5") (pintype "bidirectional"))
      (node (ref "MOS2") (pin "6") (pinfunction "6_6") (pintype "bidirectional"))
    )
    (net (code "44") (name "Net-(DCDC3-PadVIN)") (class "Default")
      (node (ref "DCDC3") (pin "VIN") (pinfunction "VIN_VIN") (pintype "bidirectional"))
      (node (ref "MOS10") (pin "1") (pinfunction "1_1") (pintype "bidirectional"))
      (node (ref "MOS10") (pin "2") (pinfunction "2_2") (pintype "bidirectional"))
      (node (ref "MOS10") (pin "5") (pinfunction "5_5") (pintype "bidirectional"))
      (node (ref "MOS10") (pin "6") (pinfunction "6_6") (pintype "bidirectional"))
    )
    (net (code "45") (name "Net-(LED0-PadCT)") (class "Default")
      (node (ref "LED0") (pin "CT") (pinfunction "CT_CT") (pintype "bidirectional"))
      (node (ref "R5") (pin "2") (pinfunction "2_2") (pintype "passive"))
    )
    (net (code "46") (name "Net-(LED1-PadCT)") (class "Default")
      (node (ref "LED1") (pin "CT") (pinfunction "CT_CT") (pintype "bidirectional"))
      (node (ref "R6") (pin "2") (pinfunction "2_2") (pintype "passive"))
    )
    (net (code "47") (name "Net-(LED2-PadCT)") (class "Default")
      (node (ref "LED2") (pin "CT") (pinfunction "CT_CT") (pintype "bidirectional"))
      (node (ref "R22") (pin "2") (pinfunction "2_2") (pintype "passive"))
    )
    (net (code "48") (name "Net-(LED3-PadCT)") (class "Default")
      (node (ref "LED3") (pin "CT") (pinfunction "CT_CT") (pintype "bidirectional"))
      (node (ref "R23") (pin "2") (pinfunction "2_2") (pintype "passive"))
    )
    (net (code "49") (name "Net-(LED4-PadCT)") (class "Default")
      (node (ref "LED4") (pin "CT") (pinfunction "CT_CT") (pintype "bidirectional"))
      (node (ref "R24") (pin "2") (pinfunction "2_2") (pintype "passive"))
    )
    (net (code "50") (name "Net-(LED5-PadCT)") (class "Default")
      (node (ref "LED5") (pin "CT") (pinfunction "CT_CT") (pintype "bidirectional"))
      (node (ref "R28") (pin "2") (pinfunction "2_2") (pintype "passive"))
    )
    (net (code "51") (name "Net-(LED6-PadCT)") (class "Default")
      (node (ref "LED6") (pin "CT") (pinfunction "CT_CT") (pintype "bidirectional"))
      (node (ref "R29") (pin "2") (pinfunction "2_2") (pintype "passive"))
    )
    (net (code "52") (name "Net-(MOS3-Pad1)") (class "Default")
      (node (ref "MOS3") (pin "1") (pinfunction "1_1") (pintype "bidirectional"))
      (node (ref "MOS3") (pin "2") (pinfunction "2_2") (pintype "bidirectional"))
      (node (ref "MOS3") (pin "5") (pinfunction "5_5") (pintype "bidirectional"))
      (node (ref "MOS3") (pin "6") (pinfunction "6_6") (pintype "bidirectional"))
      (node (ref "MOS7") (pin "1") (pinfunction "1_1") (pintype "bidirectional"))
      (node (ref "MOS7") (pin "2") (pinfunction "2_2") (pintype "bidirectional"))
      (node (ref "MOS7") (pin "5") (pinfunction "5_5") (pintype "bidirectional"))
      (node (ref "MOS7") (pin "6") (pinfunction "6_6") (pintype "bidirectional"))
    )
    (net (code "53") (name "Net-(MOS4-Pad1)") (class "Default")
      (node (ref "MOS4") (pin "1") (pinfunction "1_1") (pintype "bidirectional"))
      (node (ref "MOS4") (pin "2") (pinfunction "2_2") (pintype "bidirectional"))
      (node (ref "MOS4") (pin "5") (pinfunction "5_5") (pintype "bidirectional"))
      (node (ref "MOS4") (pin "6") (pinfunction "6_6") (pintype "bidirectional"))
      (node (ref "MOS6") (pin "1") (pinfunction "1_1") (pintype "bidirectional"))
      (node (ref "MOS6") (pin "2") (pinfunction "2_2") (pintype "bidirectional"))
      (node (ref "MOS6") (pin "5") (pinfunction "5_5") (pintype "bidirectional"))
      (node (ref "MOS6") (pin "6") (pinfunction "6_6") (pintype "bidirectional"))
    )
    (net (code "54") (name "Net-(MOS5-Pad1)") (class "Default")
      (node (ref "MOS5") (pin "1") (pinfunction "1_1") (pintype "bidirectional"))
      (node (ref "MOS5") (pin "2") (pinfunction "2_2") (pintype "bidirectional"))
      (node (ref "MOS5") (pin "5") (pinfunction "5_5") (pintype "bidirectional"))
      (node (ref "MOS5") (pin "6") (pinfunction "6_6") (pintype "bidirectional"))
      (node (ref "R13") (pin "1") (pinfunction "1_1") (pintype "passive"))
      (node (ref "R14") (pin "2") (pinfunction "2_2") (pintype "passive"))
    )
    (net (code "55") (name "Net-(MOS8-Pad1)") (class "Default")
      (node (ref "MOS8") (pin "1") (pinfunction "1_1") (pintype "bidirectional"))
      (node (ref "MOS8") (pin "2") (pinfunction "2_2") (pintype "bidirectional"))
      (node (ref "MOS8") (pin "5") (pinfunction "5_5") (pintype "bidirectional"))
      (node (ref "MOS8") (pin "6") (pinfunction "6_6") (pintype "bidirectional"))
      (node (ref "MOS9") (pin "1") (pinfunction "1_1") (pintype "bidirectional"))
      (node (ref "MOS9") (pin "2") (pinfunction "2_2") (pintype "bidirectional"))
      (node (ref "MOS9") (pin "5") (pinfunction "5_5") (pintype "bidirectional"))
      (node (ref "MOS9") (pin "6") (pinfunction "6_6") (pintype "bidirectional"))
    )
    (net (code "56") (name "Net-(PWR-PadCT)") (class "Default")
      (node (ref "PWR") (pin "CT") (pinfunction "CT_CT") (pintype "bidirectional"))
      (node (ref "R3") (pin "2") (pinfunction "2_2") (pintype "passive"))
    )
    (net (code "57") (name "Net-(PWR1-PadCT)") (class "Default")
      (node (ref "PWR1") (pin "CT") (pinfunction "CT_CT") (pintype "bidirectional"))
      (node (ref "R21") (pin "2") (pinfunction "2_2") (pintype "passive"))
    )
    (net (code "58") (name "Net-(PWR2-PadCT)") (class "Default")
      (node (ref "PWR2") (pin "CT") (pinfunction "CT_CT") (pintype "bidirectional"))
      (node (ref "R27") (pin "2") (pinfunction "2_2") (pintype "passive"))
    )
    (net (code "59") (name "OSC_IN1") (class "Default")
      (node (ref "STM1") (pin "PF0") (pinfunction "PF0_PF0") (pintype "bidirectional"))
    )
    (net (code "60") (name "OSC_IN2") (class "Default")
      (node (ref "U$1") (pin "PF0") (pinfunction "PF0_PF0") (pintype "bidirectional"))
    )
    (net (code "61") (name "OSC_OUT1") (class "Default")
      (node (ref "STM1") (pin "PF1") (pinfunction "PF1_PF1") (pintype "bidirectional"))
    )
    (net (code "62") (name "OSC_OUT2") (class "Default")
      (node (ref "U$1") (pin "PF1") (pinfunction "PF1_PF1") (pintype "bidirectional"))
    )
    (net (code "63") (name "PWM") (class "Default")
      (node (ref "SV") (pin "P$1") (pinfunction "P$1_P$1") (pintype "bidirectional"))
      (node (ref "U$1") (pin "PA5/SPI1_SCK") (pinfunction "PA5/SPI1_SCK_PA5/SPI1_SCK") (pintype "bidirectional"))
    )
    (net (code "64") (name "SCK") (class "Default")
      (node (ref "R11") (pin "1") (pinfunction "1_1") (pintype "passive"))
      (node (ref "STM0") (pin "PA5/SPI1_SCK") (pinfunction "PA5/SPI1_SCK_PA5/SPI1_SCK") (pintype "bidirectional"))
    )
    (net (code "65") (name "SCL0") (class "Default")
      (node (ref "BMP1") (pin "P3") (pinfunction "SCL_P3") (pintype "bidirectional"))
      (node (ref "BMX1") (pin "SCL") (pinfunction "SCL_SCL") (pintype "bidirectional"))
      (node (ref "STM0") (pin "PA15/I2C1_SCL") (pinfunction "PA15/I2C1_SCL_PA15/I2C1_SCL") (pintype "bidirectional"))
    )
    (net (code "66") (name "SCL1") (class "Default")
      (node (ref "BMP3") (pin "P3") (pinfunction "SCL_P3") (pintype "bidirectional"))
      (node (ref "STM1") (pin "PA15/I2C1_SCL") (pinfunction "PA15/I2C1_SCL_PA15/I2C1_SCL") (pintype "bidirectional"))
    )
    (net (code "67") (name "SCL2") (class "Default")
      (node (ref "BMP2") (pin "P3") (pinfunction "SCL_P3") (pintype "bidirectional"))
      (node (ref "BMX2") (pin "SCL") (pinfunction "SCL_SCL") (pintype "bidirectional"))
      (node (ref "U$1") (pin "PA15/I2C1_SCL") (pinfunction "PA15/I2C1_SCL_PA15/I2C1_SCL") (pintype "bidirectional"))
    )
    (net (code "68") (name "SDA0") (class "Default")
      (node (ref "BMP1") (pin "P4") (pinfunction "SDA_P4") (pintype "bidirectional"))
      (node (ref "BMX1") (pin "SDA") (pinfunction "SDA_SDA") (pintype "bidirectional"))
      (node (ref "STM0") (pin "PB7/I2C1_SDA") (pinfunction "PB7/I2C1_SDA_PB7/I2C1_SDA") (pintype "bidirectional"))
    )
    (net (code "69") (name "SDA1") (class "Default")
      (node (ref "BMP3") (pin "P4") (pinfunction "SDA_P4") (pintype "bidirectional"))
      (node (ref "STM1") (pin "PB7/I2C1_SDA") (pinfunction "PB7/I2C1_SDA_PB7/I2C1_SDA") (pintype "bidirectional"))
    )
    (net (code "70") (name "SDA2") (class "Default")
      (node (ref "BMP2") (pin "P4") (pinfunction "SDA_P4") (pintype "bidirectional"))
      (node (ref "BMX2") (pin "SDA") (pinfunction "SDA_SDA") (pintype "bidirectional"))
      (node (ref "U$1") (pin "PB7/I2C1_SDA") (pinfunction "PB7/I2C1_SDA_PB7/I2C1_SDA") (pintype "bidirectional"))
    )
    (net (code "71") (name "SW") (class "Default")
      (node (ref "MOS1") (pin "3") (pinfunction "3_3") (pintype "bidirectional"))
      (node (ref "MOS10") (pin "3") (pinfunction "3_3") (pintype "bidirectional"))
      (node (ref "MOS2") (pin "3") (pinfunction "3_3") (pintype "bidirectional"))
      (node (ref "R15") (pin "1") (pinfunction "1_1") (pintype "passive"))
      (node (ref "R16") (pin "1") (pinfunction "1_1") (pintype "passive"))
      (node (ref "R18") (pin "1") (pinfunction "1_1") (pintype "passive"))
      (node (ref "SW1") (pin "L") (pinfunction "L_L") (pintype "bidirectional"))
    )
    (net (code "72") (name "SWCLK") (class "Default")
      (node (ref "JP1") (pin "3") (pinfunction "3_3") (pintype "passive"))
      (node (ref "STM0") (pin "PA14/SWCLK") (pinfunction "PA14/SWCLK_PA14/SWCLK") (pintype "bidirectional"))
    )
    (net (code "73") (name "SWCLK1") (class "Default")
      (node (ref "JP3") (pin "3") (pinfunction "3_3") (pintype "passive"))
      (node (ref "STM1") (pin "PA14/SWCLK") (pinfunction "PA14/SWCLK_PA14/SWCLK") (pintype "bidirectional"))
    )
    (net (code "74") (name "SWCLK2") (class "Default")
      (node (ref "JP4") (pin "3") (pinfunction "3_3") (pintype "passive"))
      (node (ref "U$1") (pin "PA14/SWCLK") (pinfunction "PA14/SWCLK_PA14/SWCLK") (pintype "bidirectional"))
    )
    (net (code "75") (name "SWDIO") (class "Default")
      (node (ref "JP1") (pin "5") (pinfunction "5_5") (pintype "passive"))
      (node (ref "STM0") (pin "PA13/SWDIO") (pinfunction "PA13/SWDIO_PA13/SWDIO") (pintype "bidirectional"))
    )
    (net (code "76") (name "SWDIO1") (class "Default")
      (node (ref "JP3") (pin "5") (pinfunction "5_5") (pintype "passive"))
      (node (ref "STM1") (pin "PA13/SWDIO") (pinfunction "PA13/SWDIO_PA13/SWDIO") (pintype "bidirectional"))
    )
    (net (code "77") (name "SWDIO2") (class "Default")
      (node (ref "JP4") (pin "5") (pinfunction "5_5") (pintype "passive"))
      (node (ref "U$1") (pin "PA13/SWDIO") (pinfunction "PA13/SWDIO_PA13/SWDIO") (pintype "bidirectional"))
    )
    (net (code "78") (name "SWO") (class "Default")
      (node (ref "JP1") (pin "1") (pinfunction "1_1") (pintype "passive"))
      (node (ref "STM0") (pin "PB3/SWO") (pinfunction "PB3/TRACESWO_PB3/SWO") (pintype "bidirectional"))
    )
    (net (code "79") (name "SWO1") (class "Default")
      (node (ref "JP3") (pin "1") (pinfunction "1_1") (pintype "passive"))
      (node (ref "STM1") (pin "PB3/SWO") (pinfunction "PB3/TRACESWO_PB3/SWO") (pintype "bidirectional"))
    )
    (net (code "80") (name "SWO2") (class "Default")
      (node (ref "JP4") (pin "1") (pinfunction "1_1") (pintype "passive"))
      (node (ref "U$1") (pin "PB3/SWO") (pinfunction "PB3/TRACESWO_PB3/SWO") (pintype "bidirectional"))
    )
    (net (code "81") (name "unconnected-(CN1-PadDAT1)") (class "Default")
      (node (ref "CN1") (pin "DAT1") (pinfunction "DAT1_DAT1") (pintype "bidirectional"))
    )
    (net (code "82") (name "unconnected-(CN1-PadDAT2)") (class "Default")
      (node (ref "CN1") (pin "DAT2") (pinfunction "DAT2_DAT2") (pintype "bidirectional"))
    )
    (net (code "83") (name "unconnected-(CN1-PadDET_A)") (class "Default")
      (node (ref "CN1") (pin "DET_A") (pinfunction "DET_A_DET_A") (pintype "bidirectional"))
    )
    (net (code "84") (name "unconnected-(CN1-PadDET_B)") (class "Default")
      (node (ref "CN1") (pin "DET_B") (pinfunction "DET_B_DET_B") (pintype "bidirectional"))
    )
    (net (code "85") (name "unconnected-(IM-IO2-Pad$P2)") (class "Default")
      (node (ref "IM") (pin "$P2") (pinfunction "IO2_$P2") (pintype "bidirectional"))
    )
    (net (code "86") (name "unconnected-(IM-IO5-Pad$P5)") (class "Default")
      (node (ref "IM") (pin "$P5") (pinfunction "IO5_$P5") (pintype "bidirectional"))
    )
    (net (code "87") (name "unconnected-(IM-IO8-Pad$P8)") (class "Default")
      (node (ref "IM") (pin "$P8") (pinfunction "IO8_$P8") (pintype "bidirectional"))
    )
    (net (code "88") (name "unconnected-(IM-MODE1{slash}IO9-Pad$P9)") (class "Default")
      (node (ref "IM") (pin "$P9") (pinfunction "MODE1/IO9_$P9") (pintype "bidirectional"))
    )
    (net (code "89") (name "unconnected-(IM-MODE2{slash}IO10-Pad$P10)") (class "Default")
      (node (ref "IM") (pin "$P10") (pinfunction "MODE2/IO10_$P10") (pintype "bidirectional"))
    )
    (net (code "90") (name "unconnected-(IM-REG-Pad$P16)") (class "Default")
      (node (ref "IM") (pin "$P16") (pinfunction "REG_$P16") (pintype "bidirectional"))
    )
    (net (code "91") (name "unconnected-(IM-SLEEP{slash}IO4-Pad$P4)") (class "Default")
      (node (ref "IM") (pin "$P4") (pinfunction "SLEEP/IO4_$P4") (pintype "bidirectional"))
    )
    (net (code "92") (name "unconnected-(IM-XMIT{slash}IO3-Pad$P3)") (class "Default")
      (node (ref "IM") (pin "$P3") (pinfunction "XMIT/IO3_$P3") (pintype "bidirectional"))
    )
    (net (code "93") (name "unconnected-(JP1-Pad4)") (class "Default")
      (node (ref "JP1") (pin "4") (pinfunction "4_4") (pintype "passive"))
    )
    (net (code "94") (name "unconnected-(JP3-Pad4)") (class "Default")
      (node (ref "JP3") (pin "4") (pinfunction "4_4") (pintype "passive"))
    )
    (net (code "95") (name "unconnected-(JP4-Pad4)") (class "Default")
      (node (ref "JP4") (pin "4") (pinfunction "4_4") (pintype "passive"))
    )
    (net (code "96") (name "unconnected-(STM0-PadPA0)") (class "Default")
      (node (ref "STM0") (pin "PA0") (pinfunction "PA0_PA0") (pintype "bidirectional"))
    )
    (net (code "97") (name "unconnected-(STM0-PadPA1)") (class "Default")
      (node (ref "STM0") (pin "PA1") (pinfunction "PA1_PA1") (pintype "bidirectional"))
    )
    (net (code "98") (name "unconnected-(STM0-PadPA2{slash}UART2_TX)") (class "Default")
      (node (ref "STM0") (pin "PA2/UART2_TX") (pinfunction "PA2/UART2_TX_PA2/UART2_TX") (pintype "bidirectional"))
    )
    (net (code "99") (name "unconnected-(STM0-PadPA3{slash}UART2_RX)") (class "Default")
      (node (ref "STM0") (pin "PA3/UART2_RX") (pinfunction "PA3/UART2_RX_PA3/UART2_RX") (pintype "bidirectional"))
    )
    (net (code "100") (name "unconnected-(STM0-PadPA8)") (class "Default")
      (node (ref "STM0") (pin "PA8") (pinfunction "PA8_PA8") (pintype "bidirectional"))
    )
    (net (code "101") (name "unconnected-(STM0-PadPA11{slash}CAN_RX)") (class "Default")
      (node (ref "STM0") (pin "PA11/CAN_RX") (pinfunction "PA11/CAN_RX_PA11/CAN_RX") (pintype "bidirectional"))
    )
    (net (code "102") (name "unconnected-(STM0-PadPA12{slash}CAN_TX)") (class "Default")
      (node (ref "STM0") (pin "PA12/CAN_TX") (pinfunction "PA12/CAN_TX_PA12/CAN_TX") (pintype "bidirectional"))
    )
    (net (code "103") (name "unconnected-(STM0-PadPB5)") (class "Default")
      (node (ref "STM0") (pin "PB5") (pinfunction "PB5_PB5") (pintype "bidirectional"))
    )
    (net (code "104") (name "unconnected-(STM0-PadPB6)") (class "Default")
      (node (ref "STM0") (pin "PB6") (pinfunction "PB6_PB6") (pintype "bidirectional"))
    )
    (net (code "105") (name "unconnected-(STM0-PadPF0)") (class "Default")
      (node (ref "STM0") (pin "PF0") (pinfunction "PF0_PF0") (pintype "bidirectional"))
    )
    (net (code "106") (name "unconnected-(STM0-PadPF1)") (class "Default")
      (node (ref "STM0") (pin "PF1") (pinfunction "PF1_PF1") (pintype "bidirectional"))
    )
    (net (code "107") (name "unconnected-(STM1-PadPA0)") (class "Default")
      (node (ref "STM1") (pin "PA0") (pinfunction "PA0_PA0") (pintype "bidirectional"))
    )
    (net (code "108") (name "unconnected-(STM1-PadPA1)") (class "Default")
      (node (ref "STM1") (pin "PA1") (pinfunction "PA1_PA1") (pintype "bidirectional"))
    )
    (net (code "109") (name "unconnected-(STM1-PadPA4{slash}SPI1_NSS)") (class "Default")
      (node (ref "STM1") (pin "PA4/SPI1_NSS") (pinfunction "PA4/SPI1_NSS_PA4/SPI1_NSS") (pintype "bidirectional"))
    )
    (net (code "110") (name "unconnected-(STM1-PadPA7{slash}SPI1_MOSI)") (class "Default")
      (node (ref "STM1") (pin "PA7/SPI1_MOSI") (pinfunction "PA7/SPI1_MOSI_PA7/SPI1_MOSI") (pintype "bidirectional"))
    )
    (net (code "111") (name "unconnected-(STM1-PadPA8)") (class "Default")
      (node (ref "STM1") (pin "PA8") (pinfunction "PA8_PA8") (pintype "bidirectional"))
    )
    (net (code "112") (name "unconnected-(STM1-PadPB5)") (class "Default")
      (node (ref "STM1") (pin "PB5") (pinfunction "PB5_PB5") (pintype "bidirectional"))
    )
    (net (code "113") (name "unconnected-(STM1-PadPB6)") (class "Default")
      (node (ref "STM1") (pin "PB6") (pinfunction "PB6_PB6") (pintype "bidirectional"))
    )
    (net (code "114") (name "unconnected-(SW1-PadR)") (class "Default")
      (node (ref "SW1") (pin "R") (pinfunction "R_R") (pintype "bidirectional"))
    )
    (net (code "115") (name "unconnected-(U$1-PadPA0)") (class "Default")
      (node (ref "U$1") (pin "PA0") (pinfunction "PA0_PA0") (pintype "bidirectional"))
    )
    (net (code "116") (name "unconnected-(U$1-PadPA1)") (class "Default")
      (node (ref "U$1") (pin "PA1") (pinfunction "PA1_PA1") (pintype "bidirectional"))
    )
    (net (code "117") (name "unconnected-(U$1-PadPA2{slash}UART2_TX)") (class "Default")
      (node (ref "U$1") (pin "PA2/UART2_TX") (pinfunction "PA2/UART2_TX_PA2/UART2_TX") (pintype "bidirectional"))
    )
    (net (code "118") (name "unconnected-(U$1-PadPA3{slash}UART2_RX)") (class "Default")
      (node (ref "U$1") (pin "PA3/UART2_RX") (pinfunction "PA3/UART2_RX_PA3/UART2_RX") (pintype "bidirectional"))
    )
    (net (code "119") (name "unconnected-(U$1-PadPA4{slash}SPI1_NSS)") (class "Default")
      (node (ref "U$1") (pin "PA4/SPI1_NSS") (pinfunction "PA4/SPI1_NSS_PA4/SPI1_NSS") (pintype "bidirectional"))
    )
    (net (code "120") (name "unconnected-(U$1-PadPA6{slash}SPI1_MISO)") (class "Default")
      (node (ref "U$1") (pin "PA6/SPI1_MISO") (pinfunction "PA6/SPI1_MISO_PA6/SPI1_MISO") (pintype "bidirectional"))
    )
    (net (code "121") (name "unconnected-(U$1-PadPA7{slash}SPI1_MOSI)") (class "Default")
      (node (ref "U$1") (pin "PA7/SPI1_MOSI") (pinfunction "PA7/SPI1_MOSI_PA7/SPI1_MOSI") (pintype "bidirectional"))
    )
    (net (code "122") (name "unconnected-(U$1-PadPA8)") (class "Default")
      (node (ref "U$1") (pin "PA8") (pinfunction "PA8_PA8") (pintype "bidirectional"))
    )
    (net (code "123") (name "unconnected-(U$1-PadPB5)") (class "Default")
      (node (ref "U$1") (pin "PB5") (pinfunction "PB5_PB5") (pintype "bidirectional"))
    )
    (net (code "124") (name "unconnected-(U$1-PadPB6)") (class "Default")
      (node (ref "U$1") (pin "PB6") (pinfunction "PB6_PB6") (pintype "bidirectional"))
    )
    (net (code "125") (name "unconnected-(U$2-1PPS-PadP5)") (class "Default")
      (node (ref "U$2") (pin "P5") (pinfunction "1PPS_P5") (pintype "bidirectional"))
    )
  )
)
